# design1.net
KiCad netlist of a schematic drawn in EAGLE
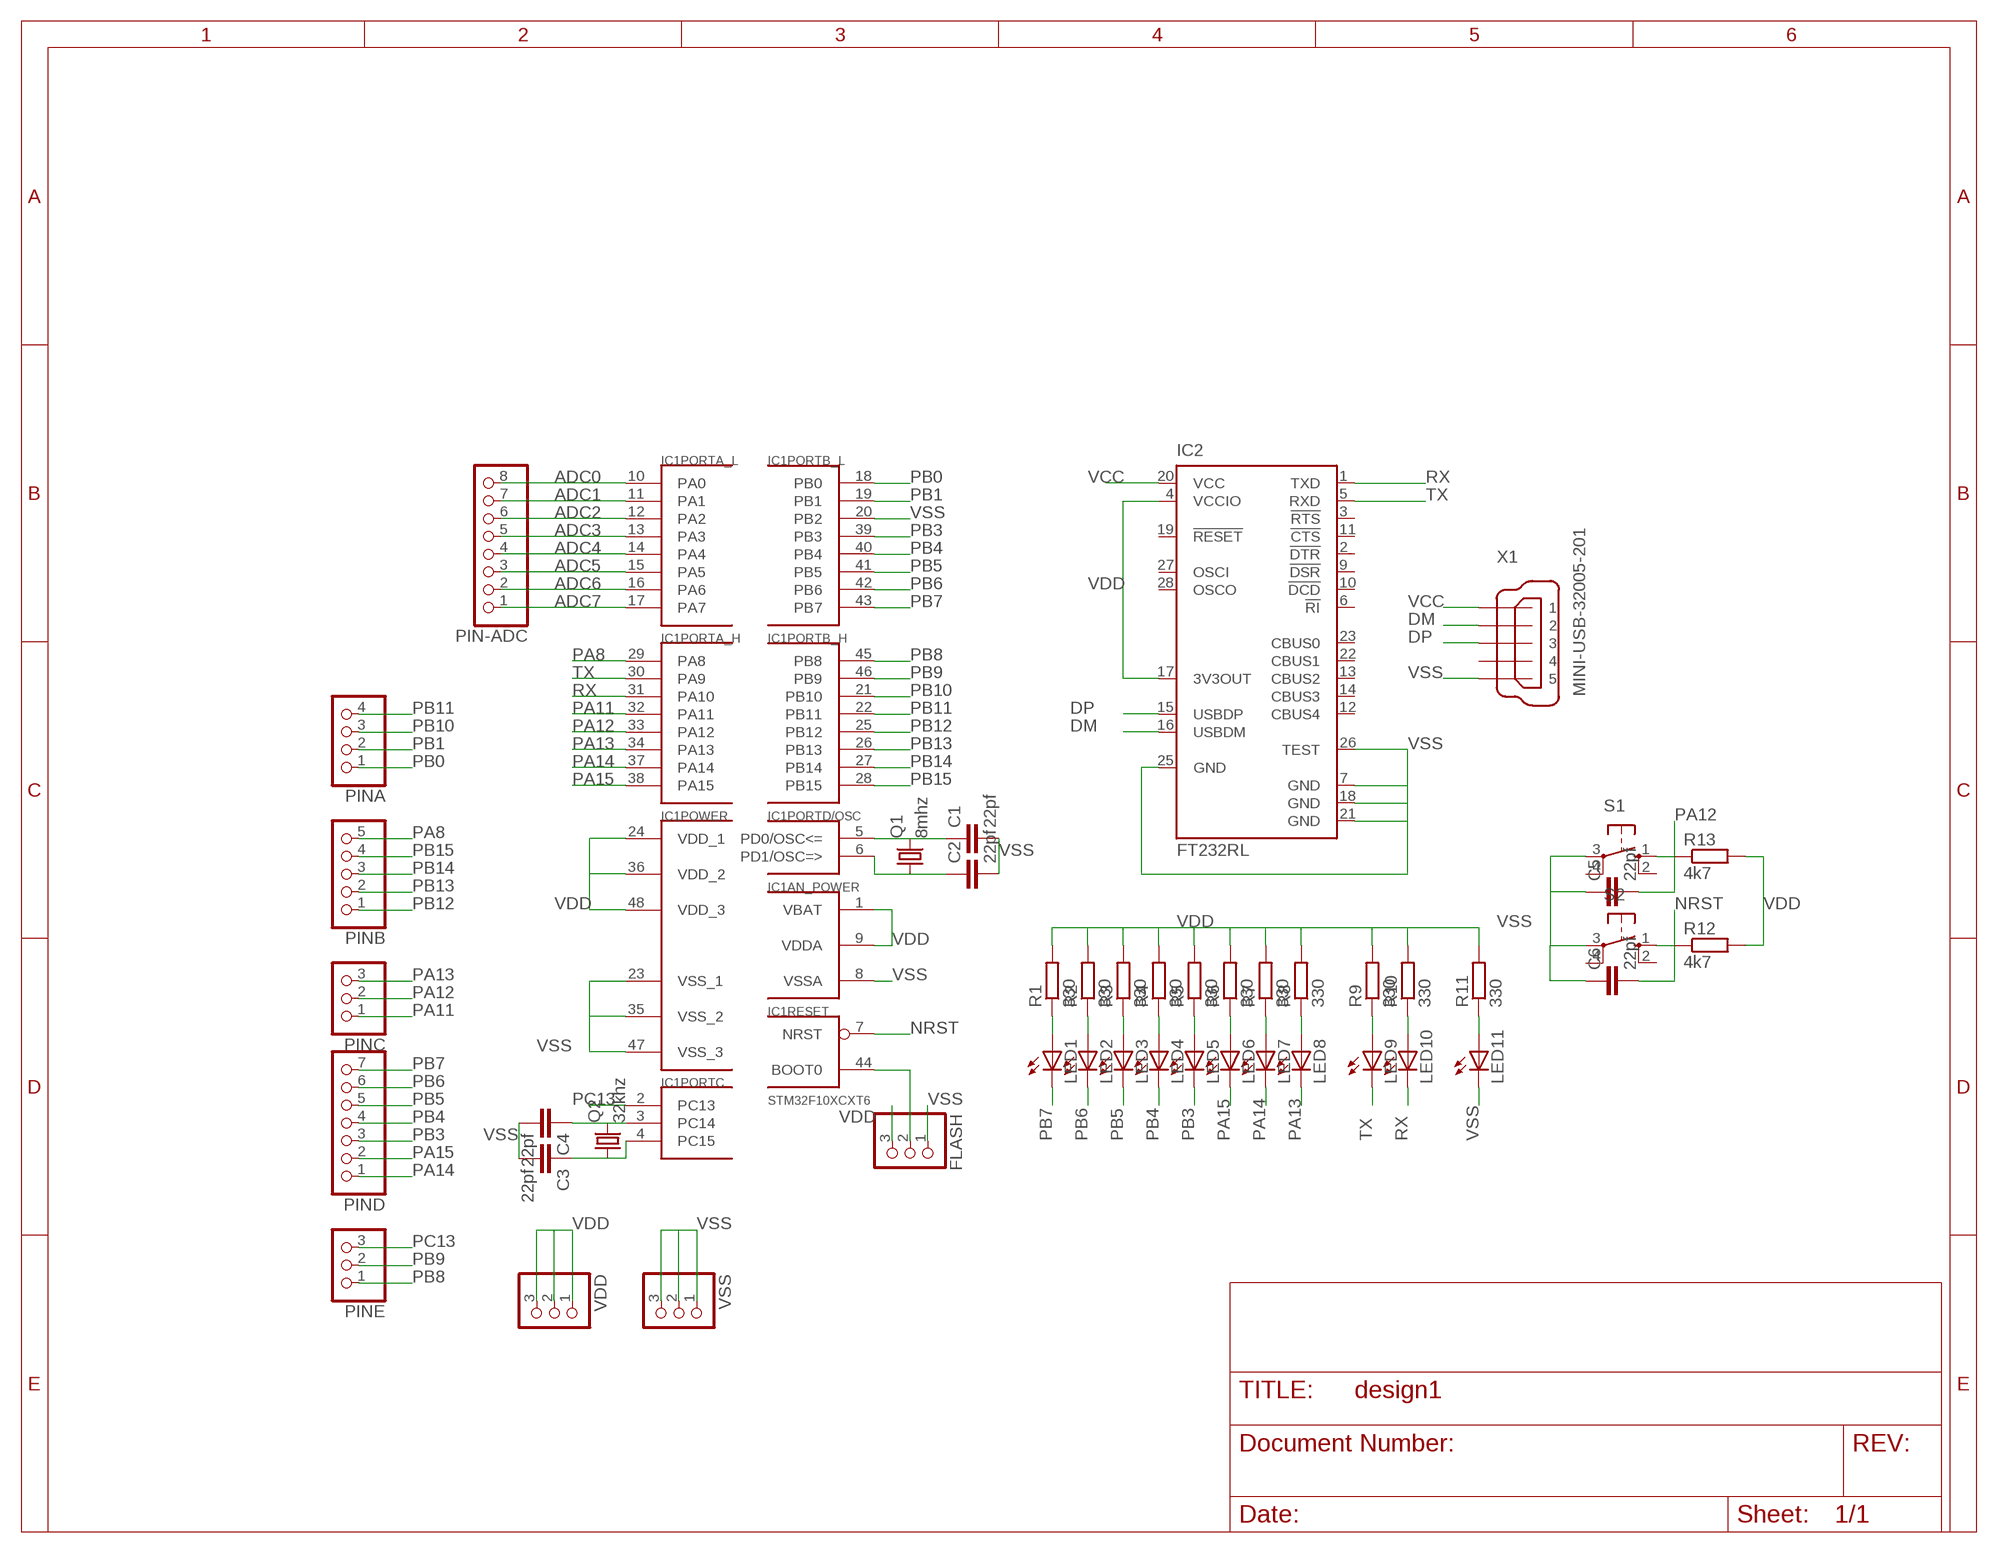
[diagram p0: schematic, sheet 1]

(export (version "E")
  (design (tool "Eeschema 10.0.6"))
  (components
    (comp (ref "C1")
      (value "22pf")
      (footprint "eagle-import:C1206")
      (libsource (lib "eagle-import") (part "C-EUC1206"))
    )
    (comp (ref "C2")
      (value "22pf")
      (footprint "eagle-import:C1206")
      (libsource (lib "eagle-import") (part "C-EUC1206"))
    )
    (comp (ref "C3")
      (value "22pf")
      (footprint "eagle-import:C1206")
      (libsource (lib "eagle-import") (part "C-EUC1206"))
    )
    (comp (ref "C4")
      (value "22pf")
      (footprint "eagle-import:C1206")
      (libsource (lib "eagle-import") (part "C-EUC1206"))
    )
    (comp (ref "C5")
      (value "22pf")
      (footprint "eagle-import:C1206")
      (libsource (lib "eagle-import") (part "C-EUC1206"))
    )
    (comp (ref "C6")
      (value "22pf")
      (footprint "eagle-import:C1206")
      (libsource (lib "eagle-import") (part "C-EUC1206"))
    )
    (comp (ref "FLASH")
      (value "PINHD-1X3")
      (footprint "eagle-import:1X03")
      (libsource (lib "eagle-import") (part "PINHD-1X3"))
    )
    (comp (ref "IC1")
      (value "STM32F10XCXT6")
      (footprint "eagle-import:TQFP48")
      (libsource (lib "eagle-import") (part "STM32F10XCXT6"))
    )
    (comp (ref "IC2")
      (value "FT232RL")
      (footprint "eagle-import:SSOP28")
      (libsource (lib "eagle-import") (part "FT232RL"))
    )
    (comp (ref "LED1")
      (value "LEDSML1206")
      (footprint "eagle-import:SML1206")
      (libsource (lib "eagle-import") (part "LEDSML1206"))
    )
    (comp (ref "LED2")
      (value "LEDSML1206")
      (footprint "eagle-import:SML1206")
      (libsource (lib "eagle-import") (part "LEDSML1206"))
    )
    (comp (ref "LED3")
      (value "LEDSML1206")
      (footprint "eagle-import:SML1206")
      (libsource (lib "eagle-import") (part "LEDSML1206"))
    )
    (comp (ref "LED4")
      (value "LEDSML1206")
      (footprint "eagle-import:SML1206")
      (libsource (lib "eagle-import") (part "LEDSML1206"))
    )
    (comp (ref "LED5")
      (value "LEDSML1206")
      (footprint "eagle-import:SML1206")
      (libsource (lib "eagle-import") (part "LEDSML1206"))
    )
    (comp (ref "LED6")
      (value "LEDSML1206")
      (footprint "eagle-import:SML1206")
      (libsource (lib "eagle-import") (part "LEDSML1206"))
    )
    (comp (ref "LED7")
      (value "LEDSML1206")
      (footprint "eagle-import:SML1206")
      (libsource (lib "eagle-import") (part "LEDSML1206"))
    )
    (comp (ref "LED8")
      (value "LEDSML1206")
      (footprint "eagle-import:SML1206")
      (libsource (lib "eagle-import") (part "LEDSML1206"))
    )
    (comp (ref "LED9")
      (value "LEDSML1206")
      (footprint "eagle-import:SML1206")
      (libsource (lib "eagle-import") (part "LEDSML1206"))
    )
    (comp (ref "LED10")
      (value "LEDSML1206")
      (footprint "eagle-import:SML1206")
      (libsource (lib "eagle-import") (part "LEDSML1206"))
    )
    (comp (ref "LED11")
      (value "LEDSML1206")
      (footprint "eagle-import:SML1206")
      (libsource (lib "eagle-import") (part "LEDSML1206"))
    )
    (comp (ref "PIN-ADC")
      (value "PINHD-1X8")
      (footprint "eagle-import:1X08")
      (libsource (lib "eagle-import") (part "PINHD-1X8"))
    )
    (comp (ref "PINA")
      (value "PINHD-1X4")
      (footprint "eagle-import:1X04")
      (libsource (lib "eagle-import") (part "PINHD-1X4"))
    )
    (comp (ref "PINB")
      (value "PINHD-1X5")
      (footprint "eagle-import:1X05")
      (libsource (lib "eagle-import") (part "PINHD-1X5"))
    )
    (comp (ref "PINC")
      (value "PINHD-1X3")
      (footprint "eagle-import:1X03")
      (libsource (lib "eagle-import") (part "PINHD-1X3"))
    )
    (comp (ref "PIND")
      (value "PINHD-1X7")
      (footprint "eagle-import:1X07")
      (libsource (lib "eagle-import") (part "PINHD-1X7"))
    )
    (comp (ref "PINE")
      (value "PINHD-1X3")
      (footprint "eagle-import:1X03")
      (libsource (lib "eagle-import") (part "PINHD-1X3"))
    )
    (comp (ref "Q1")
      (value "8mhz")
      (footprint "eagle-import:HC49U-V")
      (libsource (lib "eagle-import") (part "CRYSTALHC49U-V"))
    )
    (comp (ref "Q2")
      (value "32khz")
      (footprint "eagle-import:TC26V")
      (libsource (lib "eagle-import") (part "CRYSTALTC26V"))
    )
    (comp (ref "R1")
      (value "330")
      (footprint "eagle-import:R1206")
      (libsource (lib "eagle-import") (part "R-EU_R1206"))
    )
    (comp (ref "R2")
      (value "330")
      (footprint "eagle-import:R1206")
      (libsource (lib "eagle-import") (part "R-EU_R1206"))
    )
    (comp (ref "R3")
      (value "330")
      (footprint "eagle-import:R1206")
      (libsource (lib "eagle-import") (part "R-EU_R1206"))
    )
    (comp (ref "R4")
      (value "330")
      (footprint "eagle-import:R1206")
      (libsource (lib "eagle-import") (part "R-EU_R1206"))
    )
    (comp (ref "R5")
      (value "330")
      (footprint "eagle-import:R1206")
      (libsource (lib "eagle-import") (part "R-EU_R1206"))
    )
    (comp (ref "R6")
      (value "330")
      (footprint "eagle-import:R1206")
      (libsource (lib "eagle-import") (part "R-EU_R1206"))
    )
    (comp (ref "R7")
      (value "330")
      (footprint "eagle-import:R1206")
      (libsource (lib "eagle-import") (part "R-EU_R1206"))
    )
    (comp (ref "R8")
      (value "330")
      (footprint "eagle-import:R1206")
      (libsource (lib "eagle-import") (part "R-EU_R1206"))
    )
    (comp (ref "R9")
      (value "330")
      (footprint "eagle-import:R1206")
      (libsource (lib "eagle-import") (part "R-EU_R1206"))
    )
    (comp (ref "R10")
      (value "330")
      (footprint "eagle-import:R1206")
      (libsource (lib "eagle-import") (part "R-EU_R1206"))
    )
    (comp (ref "R11")
      (value "330")
      (footprint "eagle-import:R1206")
      (libsource (lib "eagle-import") (part "R-EU_R1206"))
    )
    (comp (ref "R12")
      (value "4k7")
      (footprint "eagle-import:R1206")
      (libsource (lib "eagle-import") (part "R-EU_R1206"))
    )
    (comp (ref "R13")
      (value "4k7")
      (footprint "eagle-import:R1206")
      (libsource (lib "eagle-import") (part "R-EU_R1206"))
    )
    (comp (ref "S1")
      (value "10-XX")
      (footprint "eagle-import:B3F-10XX")
      (fields (field (name "MPN") "B3F-1000"))
      (libsource (lib "eagle-import") (part "10-XX"))
    )
    (comp (ref "S2")
      (value "10-XX")
      (footprint "eagle-import:B3F-10XX")
      (fields (field (name "MPN") "B3F-1000"))
      (libsource (lib "eagle-import") (part "10-XX"))
    )
    (comp (ref "VDD")
      (value "PINHD-1X3")
      (footprint "eagle-import:1X03")
      (libsource (lib "eagle-import") (part "PINHD-1X3"))
    )
    (comp (ref "VSS")
      (value "PINHD-1X3")
      (footprint "eagle-import:1X03")
      (libsource (lib "eagle-import") (part "PINHD-1X3"))
    )
    (comp (ref "X1")
      (value "MINI-USB-32005-201")
      (footprint "eagle-import:32005-201")
      (libsource (lib "eagle-import") (part "MINI-USB-32005-201"))
    )
  )
  (nets
    (net (code "1") (name "/ADC0") (class "Default")
      (node (ref "IC1") (pin "10") (pinfunction "PA0_10") (pintype "bidirectional"))
      (node (ref "PIN-ADC") (pin "8") (pinfunction "8_8") (pintype "passive"))
    )
    (net (code "2") (name "/ADC1") (class "Default")
      (node (ref "IC1") (pin "11") (pinfunction "PA1_11") (pintype "bidirectional"))
      (node (ref "PIN-ADC") (pin "7") (pinfunction "7_7") (pintype "passive"))
    )
    (net (code "3") (name "/ADC2") (class "Default")
      (node (ref "IC1") (pin "12") (pinfunction "PA2_12") (pintype "bidirectional"))
      (node (ref "PIN-ADC") (pin "6") (pinfunction "6_6") (pintype "passive"))
    )
    (net (code "4") (name "/ADC3") (class "Default")
      (node (ref "IC1") (pin "13") (pinfunction "PA3_13") (pintype "bidirectional"))
      (node (ref "PIN-ADC") (pin "5") (pinfunction "5_5") (pintype "passive"))
    )
    (net (code "5") (name "/ADC4") (class "Default")
      (node (ref "IC1") (pin "14") (pinfunction "PA4_14") (pintype "bidirectional"))
      (node (ref "PIN-ADC") (pin "4") (pinfunction "4_4") (pintype "passive"))
    )
    (net (code "6") (name "/ADC5") (class "Default")
      (node (ref "IC1") (pin "15") (pinfunction "PA5_15") (pintype "bidirectional"))
      (node (ref "PIN-ADC") (pin "3") (pinfunction "3_3") (pintype "passive"))
    )
    (net (code "7") (name "/ADC6") (class "Default")
      (node (ref "IC1") (pin "16") (pinfunction "PA6_16") (pintype "bidirectional"))
      (node (ref "PIN-ADC") (pin "2") (pinfunction "2_2") (pintype "passive"))
    )
    (net (code "8") (name "/ADC7") (class "Default")
      (node (ref "IC1") (pin "17") (pinfunction "PA7_17") (pintype "bidirectional"))
      (node (ref "PIN-ADC") (pin "1") (pinfunction "1_1") (pintype "passive"))
    )
    (net (code "9") (name "/DM") (class "Default")
      (node (ref "IC2") (pin "16") (pinfunction "USBDM_16") (pintype "bidirectional"))
      (node (ref "X1") (pin "2") (pinfunction "2_2") (pintype "passive"))
    )
    (net (code "10") (name "/DP") (class "Default")
      (node (ref "IC2") (pin "15") (pinfunction "USBDP_15") (pintype "bidirectional"))
      (node (ref "X1") (pin "3") (pinfunction "3_3") (pintype "passive"))
    )
    (net (code "11") (name "/NRST") (class "Default")
      (node (ref "C6") (pin "2") (pinfunction "2_2") (pintype "passive"))
      (node (ref "IC1") (pin "7") (pinfunction "NRST_7") (pintype "input"))
      (node (ref "R12") (pin "1") (pinfunction "1_1") (pintype "passive"))
      (node (ref "S2") (pin "1") (pinfunction "S_1") (pintype "passive"))
    )
    (net (code "12") (name "/PA8") (class "Default")
      (node (ref "IC1") (pin "29") (pinfunction "PA8_29") (pintype "bidirectional"))
      (node (ref "PINB") (pin "5") (pinfunction "5_5") (pintype "passive"))
    )
    (net (code "13") (name "/PA11") (class "Default")
      (node (ref "IC1") (pin "32") (pinfunction "PA11_32") (pintype "bidirectional"))
      (node (ref "PINC") (pin "1") (pinfunction "1_1") (pintype "passive"))
    )
    (net (code "14") (name "/PA12") (class "Default")
      (node (ref "C5") (pin "2") (pinfunction "2_2") (pintype "passive"))
      (node (ref "IC1") (pin "33") (pinfunction "PA12_33") (pintype "bidirectional"))
      (node (ref "PINC") (pin "2") (pinfunction "2_2") (pintype "passive"))
      (node (ref "R13") (pin "1") (pinfunction "1_1") (pintype "passive"))
      (node (ref "S1") (pin "1") (pinfunction "S_1") (pintype "passive"))
    )
    (net (code "15") (name "/PA13") (class "Default")
      (node (ref "IC1") (pin "34") (pinfunction "PA13_34") (pintype "bidirectional"))
      (node (ref "LED8") (pin "C") (pinfunction "C_C") (pintype "passive"))
      (node (ref "PINC") (pin "3") (pinfunction "3_3") (pintype "passive"))
    )
    (net (code "16") (name "/PA14") (class "Default")
      (node (ref "IC1") (pin "37") (pinfunction "PA14_37") (pintype "bidirectional"))
      (node (ref "LED7") (pin "C") (pinfunction "C_C") (pintype "passive"))
      (node (ref "PIND") (pin "1") (pinfunction "1_1") (pintype "passive"))
    )
    (net (code "17") (name "/PA15") (class "Default")
      (node (ref "IC1") (pin "38") (pinfunction "PA15_38") (pintype "bidirectional"))
      (node (ref "LED6") (pin "C") (pinfunction "C_C") (pintype "passive"))
      (node (ref "PIND") (pin "2") (pinfunction "2_2") (pintype "passive"))
    )
    (net (code "18") (name "/PB0") (class "Default")
      (node (ref "IC1") (pin "18") (pinfunction "PB0_18") (pintype "bidirectional"))
      (node (ref "PINA") (pin "1") (pinfunction "1_1") (pintype "passive"))
    )
    (net (code "19") (name "/PB1") (class "Default")
      (node (ref "IC1") (pin "19") (pinfunction "PB1_19") (pintype "bidirectional"))
      (node (ref "PINA") (pin "2") (pinfunction "2_2") (pintype "passive"))
    )
    (net (code "20") (name "/PB3") (class "Default")
      (node (ref "IC1") (pin "39") (pinfunction "PB3_39") (pintype "bidirectional"))
      (node (ref "LED5") (pin "C") (pinfunction "C_C") (pintype "passive"))
      (node (ref "PIND") (pin "3") (pinfunction "3_3") (pintype "passive"))
    )
    (net (code "21") (name "/PB4") (class "Default")
      (node (ref "IC1") (pin "40") (pinfunction "PB4_40") (pintype "bidirectional"))
      (node (ref "LED4") (pin "C") (pinfunction "C_C") (pintype "passive"))
      (node (ref "PIND") (pin "4") (pinfunction "4_4") (pintype "passive"))
    )
    (net (code "22") (name "/PB5") (class "Default")
      (node (ref "IC1") (pin "41") (pinfunction "PB5_41") (pintype "bidirectional"))
      (node (ref "LED3") (pin "C") (pinfunction "C_C") (pintype "passive"))
      (node (ref "PIND") (pin "5") (pinfunction "5_5") (pintype "passive"))
    )
    (net (code "23") (name "/PB6") (class "Default")
      (node (ref "IC1") (pin "42") (pinfunction "PB6_42") (pintype "bidirectional"))
      (node (ref "LED2") (pin "C") (pinfunction "C_C") (pintype "passive"))
      (node (ref "PIND") (pin "6") (pinfunction "6_6") (pintype "passive"))
    )
    (net (code "24") (name "/PB7") (class "Default")
      (node (ref "IC1") (pin "43") (pinfunction "PB7_43") (pintype "bidirectional"))
      (node (ref "LED1") (pin "C") (pinfunction "C_C") (pintype "passive"))
      (node (ref "PIND") (pin "7") (pinfunction "7_7") (pintype "passive"))
    )
    (net (code "25") (name "/PB8") (class "Default")
      (node (ref "IC1") (pin "45") (pinfunction "PB8_45") (pintype "bidirectional"))
      (node (ref "PINE") (pin "1") (pinfunction "1_1") (pintype "passive"))
    )
    (net (code "26") (name "/PB9") (class "Default")
      (node (ref "IC1") (pin "46") (pinfunction "PB9_46") (pintype "bidirectional"))
      (node (ref "PINE") (pin "2") (pinfunction "2_2") (pintype "passive"))
    )
    (net (code "27") (name "/PB10") (class "Default")
      (node (ref "IC1") (pin "21") (pinfunction "PB10_21") (pintype "bidirectional"))
      (node (ref "PINA") (pin "3") (pinfunction "3_3") (pintype "passive"))
    )
    (net (code "28") (name "/PB11") (class "Default")
      (node (ref "IC1") (pin "22") (pinfunction "PB11_22") (pintype "bidirectional"))
      (node (ref "PINA") (pin "4") (pinfunction "4_4") (pintype "passive"))
    )
    (net (code "29") (name "/PB12") (class "Default")
      (node (ref "IC1") (pin "25") (pinfunction "PB12_25") (pintype "bidirectional"))
      (node (ref "PINB") (pin "1") (pinfunction "1_1") (pintype "passive"))
    )
    (net (code "30") (name "/PB13") (class "Default")
      (node (ref "IC1") (pin "26") (pinfunction "PB13_26") (pintype "bidirectional"))
      (node (ref "PINB") (pin "2") (pinfunction "2_2") (pintype "passive"))
    )
    (net (code "31") (name "/PB14") (class "Default")
      (node (ref "IC1") (pin "27") (pinfunction "PB14_27") (pintype "bidirectional"))
      (node (ref "PINB") (pin "3") (pinfunction "3_3") (pintype "passive"))
    )
    (net (code "32") (name "/PB15") (class "Default")
      (node (ref "IC1") (pin "28") (pinfunction "PB15_28") (pintype "bidirectional"))
      (node (ref "PINB") (pin "4") (pinfunction "4_4") (pintype "passive"))
    )
    (net (code "33") (name "/PC13") (class "Default")
      (node (ref "IC1") (pin "2") (pinfunction "PC13_2") (pintype "bidirectional"))
      (node (ref "PINE") (pin "3") (pinfunction "3_3") (pintype "passive"))
    )
    (net (code "34") (name "/RX") (class "Default")
      (node (ref "IC1") (pin "31") (pinfunction "PA10_31") (pintype "bidirectional"))
      (node (ref "IC2") (pin "1") (pinfunction "TXD_1") (pintype "output"))
      (node (ref "LED10") (pin "C") (pinfunction "C_C") (pintype "passive"))
    )
    (net (code "35") (name "/TX") (class "Default")
      (node (ref "IC1") (pin "30") (pinfunction "PA9_30") (pintype "bidirectional"))
      (node (ref "IC2") (pin "5") (pinfunction "RXD_5") (pintype "input"))
      (node (ref "LED9") (pin "C") (pinfunction "C_C") (pintype "passive"))
    )
    (net (code "36") (name "/VCC") (class "Default")
      (node (ref "IC2") (pin "20") (pinfunction "VCC_20") (pintype "power_in"))
      (node (ref "X1") (pin "1") (pinfunction "1_1") (pintype "passive"))
    )
    (net (code "37") (name "/VDD") (class "Default")
      (node (ref "FLASH") (pin "3") (pinfunction "3_3") (pintype "passive"))
      (node (ref "IC1") (pin "1") (pinfunction "VBAT_1") (pintype "power_in"))
      (node (ref "IC1") (pin "24") (pinfunction "VDD_1_24") (pintype "power_in"))
      (node (ref "IC1") (pin "36") (pinfunction "VDD_2_36") (pintype "power_in"))
      (node (ref "IC1") (pin "48") (pinfunction "VDD_3_48") (pintype "power_in"))
      (node (ref "IC1") (pin "9") (pinfunction "VDDA_9") (pintype "power_in"))
      (node (ref "IC2") (pin "17") (pinfunction "3V3OUT_17") (pintype "output"))
      (node (ref "IC2") (pin "4") (pinfunction "VCCIO_4") (pintype "power_in"))
      (node (ref "R1") (pin "2") (pinfunction "2_2") (pintype "passive"))
      (node (ref "R10") (pin "2") (pinfunction "2_2") (pintype "passive"))
      (node (ref "R11") (pin "2") (pinfunction "2_2") (pintype "passive"))
      (node (ref "R12") (pin "2") (pinfunction "2_2") (pintype "passive"))
      (node (ref "R13") (pin "2") (pinfunction "2_2") (pintype "passive"))
      (node (ref "R2") (pin "2") (pinfunction "2_2") (pintype "passive"))
      (node (ref "R3") (pin "2") (pinfunction "2_2") (pintype "passive"))
      (node (ref "R4") (pin "2") (pinfunction "2_2") (pintype "passive"))
      (node (ref "R5") (pin "2") (pinfunction "2_2") (pintype "passive"))
      (node (ref "R6") (pin "2") (pinfunction "2_2") (pintype "passive"))
      (node (ref "R7") (pin "2") (pinfunction "2_2") (pintype "passive"))
      (node (ref "R8") (pin "2") (pinfunction "2_2") (pintype "passive"))
      (node (ref "R9") (pin "2") (pinfunction "2_2") (pintype "passive"))
      (node (ref "VDD") (pin "1") (pinfunction "1_1") (pintype "passive"))
      (node (ref "VDD") (pin "2") (pinfunction "2_2") (pintype "passive"))
      (node (ref "VDD") (pin "3") (pinfunction "3_3") (pintype "passive"))
    )
    (net (code "38") (name "/VSS") (class "Default")
      (node (ref "C1") (pin "2") (pinfunction "2_2") (pintype "passive"))
      (node (ref "C2") (pin "2") (pinfunction "2_2") (pintype "passive"))
      (node (ref "C3") (pin "2") (pinfunction "2_2") (pintype "passive"))
      (node (ref "C4") (pin "2") (pinfunction "2_2") (pintype "passive"))
      (node (ref "C5") (pin "1") (pinfunction "1_1") (pintype "passive"))
      (node (ref "C6") (pin "1") (pinfunction "1_1") (pintype "passive"))
      (node (ref "FLASH") (pin "1") (pinfunction "1_1") (pintype "passive"))
      (node (ref "IC1") (pin "20") (pinfunction "PB2_20") (pintype "bidirectional"))
      (node (ref "IC1") (pin "23") (pinfunction "VSS_1_23") (pintype "power_in"))
      (node (ref "IC1") (pin "35") (pinfunction "VSS_2_35") (pintype "power_in"))
      (node (ref "IC1") (pin "47") (pinfunction "VSS_3_47") (pintype "power_in"))
      (node (ref "IC1") (pin "8") (pinfunction "VSSA_8") (pintype "power_in"))
      (node (ref "IC2") (pin "18") (pinfunction "GND_18") (pintype "power_in"))
      (node (ref "IC2") (pin "21") (pinfunction "GND_21") (pintype "power_in"))
      (node (ref "IC2") (pin "25") (pinfunction "GND_25") (pintype "power_in"))
      (node (ref "IC2") (pin "26") (pinfunction "TEST_26") (pintype "input"))
      (node (ref "IC2") (pin "7") (pinfunction "GND_7") (pintype "power_in"))
      (node (ref "LED11") (pin "C") (pinfunction "C_C") (pintype "passive"))
      (node (ref "S1") (pin "3") (pinfunction "P_3") (pintype "passive"))
      (node (ref "S2") (pin "3") (pinfunction "P_3") (pintype "passive"))
      (node (ref "VSS") (pin "1") (pinfunction "1_1") (pintype "passive"))
      (node (ref "VSS") (pin "2") (pinfunction "2_2") (pintype "passive"))
      (node (ref "VSS") (pin "3") (pinfunction "3_3") (pintype "passive"))
      (node (ref "X1") (pin "5") (pinfunction "5_5") (pintype "passive"))
    )
    (net (code "39") (name "Net-(IC1F-PC14)") (class "Default")
      (node (ref "C4") (pin "1") (pinfunction "1_1") (pintype "passive"))
      (node (ref "IC1") (pin "3") (pinfunction "PC14_3") (pintype "bidirectional"))
      (node (ref "Q2") (pin "2") (pinfunction "2_2") (pintype "passive"))
    )
    (net (code "40") (name "Net-(IC1F-PC15)") (class "Default")
      (node (ref "C3") (pin "1") (pinfunction "1_1") (pintype "passive"))
      (node (ref "IC1") (pin "4") (pinfunction "PC15_4") (pintype "bidirectional"))
      (node (ref "Q2") (pin "1") (pinfunction "1_1") (pintype "passive"))
    )
    (net (code "41") (name "Net-(IC1G-PD0{slash}OSC<=)") (class "Default")
      (node (ref "C1") (pin "1") (pinfunction "1_1") (pintype "passive"))
      (node (ref "IC1") (pin "5") (pinfunction "PD0/OSC<=_5") (pintype "bidirectional"))
      (node (ref "Q1") (pin "2") (pinfunction "2_2") (pintype "passive"))
    )
    (net (code "42") (name "Net-(IC1G-PD1{slash}OSC=>)") (class "Default")
      (node (ref "C2") (pin "1") (pinfunction "1_1") (pintype "passive"))
      (node (ref "IC1") (pin "6") (pinfunction "PD1/OSC=>_6") (pintype "bidirectional"))
      (node (ref "Q1") (pin "1") (pinfunction "1_1") (pintype "passive"))
    )
    (net (code "43") (name "Net-(IC1I-BOOT0)") (class "Default")
      (node (ref "FLASH") (pin "2") (pinfunction "2_2") (pintype "passive"))
      (node (ref "IC1") (pin "44") (pinfunction "BOOT0_44") (pintype "input"))
    )
    (net (code "44") (name "Net-(LED1-PadA)") (class "Default")
      (node (ref "LED1") (pin "A") (pinfunction "A_A") (pintype "passive"))
      (node (ref "R1") (pin "1") (pinfunction "1_1") (pintype "passive"))
    )
    (net (code "45") (name "Net-(LED2-PadA)") (class "Default")
      (node (ref "LED2") (pin "A") (pinfunction "A_A") (pintype "passive"))
      (node (ref "R2") (pin "1") (pinfunction "1_1") (pintype "passive"))
    )
    (net (code "46") (name "Net-(LED3-PadA)") (class "Default")
      (node (ref "LED3") (pin "A") (pinfunction "A_A") (pintype "passive"))
      (node (ref "R3") (pin "1") (pinfunction "1_1") (pintype "passive"))
    )
    (net (code "47") (name "Net-(LED4-PadA)") (class "Default")
      (node (ref "LED4") (pin "A") (pinfunction "A_A") (pintype "passive"))
      (node (ref "R4") (pin "1") (pinfunction "1_1") (pintype "passive"))
    )
    (net (code "48") (name "Net-(LED5-PadA)") (class "Default")
      (node (ref "LED5") (pin "A") (pinfunction "A_A") (pintype "passive"))
      (node (ref "R5") (pin "1") (pinfunction "1_1") (pintype "passive"))
    )
    (net (code "49") (name "Net-(LED6-PadA)") (class "Default")
      (node (ref "LED6") (pin "A") (pinfunction "A_A") (pintype "passive"))
      (node (ref "R6") (pin "1") (pinfunction "1_1") (pintype "passive"))
    )
    (net (code "50") (name "Net-(LED7-PadA)") (class "Default")
      (node (ref "LED7") (pin "A") (pinfunction "A_A") (pintype "passive"))
      (node (ref "R7") (pin "1") (pinfunction "1_1") (pintype "passive"))
    )
    (net (code "51") (name "Net-(LED8-PadA)") (class "Default")
      (node (ref "LED8") (pin "A") (pinfunction "A_A") (pintype "passive"))
      (node (ref "R8") (pin "1") (pinfunction "1_1") (pintype "passive"))
    )
    (net (code "52") (name "Net-(LED9-PadA)") (class "Default")
      (node (ref "LED9") (pin "A") (pinfunction "A_A") (pintype "passive"))
      (node (ref "R9") (pin "1") (pinfunction "1_1") (pintype "passive"))
    )
    (net (code "53") (name "Net-(LED10-PadA)") (class "Default")
      (node (ref "LED10") (pin "A") (pinfunction "A_A") (pintype "passive"))
      (node (ref "R10") (pin "1") (pinfunction "1_1") (pintype "passive"))
    )
    (net (code "54") (name "Net-(LED11-PadA)") (class "Default")
      (node (ref "LED11") (pin "A") (pinfunction "A_A") (pintype "passive"))
      (node (ref "R11") (pin "1") (pinfunction "1_1") (pintype "passive"))
    )
    (net (code "55") (name "unconnected-(IC2-CBUS0-Pad23)") (class "Default")
      (node (ref "IC2") (pin "23") (pinfunction "CBUS0_23") (pintype "bidirectional"))
    )
    (net (code "56") (name "unconnected-(IC2-CBUS1-Pad22)") (class "Default")
      (node (ref "IC2") (pin "22") (pinfunction "CBUS1_22") (pintype "bidirectional"))
    )
    (net (code "57") (name "unconnected-(IC2-CBUS2-Pad13)") (class "Default")
      (node (ref "IC2") (pin "13") (pinfunction "CBUS2_13") (pintype "bidirectional"))
    )
    (net (code "58") (name "unconnected-(IC2-CBUS3-Pad14)") (class "Default")
      (node (ref "IC2") (pin "14") (pinfunction "CBUS3_14") (pintype "bidirectional"))
    )
    (net (code "59") (name "unconnected-(IC2-CBUS4-Pad12)") (class "Default")
      (node (ref "IC2") (pin "12") (pinfunction "CBUS4_12") (pintype "bidirectional"))
    )
    (net (code "60") (name "unconnected-(IC2-OSCI-Pad27)") (class "Default")
      (node (ref "IC2") (pin "27") (pinfunction "OSCI_27") (pintype "input"))
    )
    (net (code "61") (name "unconnected-(IC2-OSCO-Pad28)") (class "Default")
      (node (ref "IC2") (pin "28") (pinfunction "OSCO_28") (pintype "output"))
    )
    (net (code "62") (name "unconnected-(IC2-~{CTS}-Pad11)") (class "Default")
      (node (ref "IC2") (pin "11") (pinfunction "~{CTS}_11") (pintype "input"))
    )
    (net (code "63") (name "unconnected-(IC2-~{DCD}-Pad10)") (class "Default")
      (node (ref "IC2") (pin "10") (pinfunction "~{DCD}_10") (pintype "input"))
    )
    (net (code "64") (name "unconnected-(IC2-~{DSR}-Pad9)") (class "Default")
      (node (ref "IC2") (pin "9") (pinfunction "~{DSR}_9") (pintype "input"))
    )
    (net (code "65") (name "unconnected-(IC2-~{DTR}-Pad2)") (class "Default")
      (node (ref "IC2") (pin "2") (pinfunction "~{DTR}_2") (pintype "output"))
    )
    (net (code "66") (name "unconnected-(IC2-~{RESET}-Pad19)") (class "Default")
      (node (ref "IC2") (pin "19") (pinfunction "~{RESET}_19") (pintype "input"))
    )
    (net (code "67") (name "unconnected-(IC2-~{RI}-Pad6)") (class "Default")
      (node (ref "IC2") (pin "6") (pinfunction "~{RI}_6") (pintype "input"))
    )
    (net (code "68") (name "unconnected-(IC2-~{RTS}-Pad3)") (class "Default")
      (node (ref "IC2") (pin "3") (pinfunction "~{RTS}_3") (pintype "output"))
    )
    (net (code "69") (name "unconnected-(S1-P1-Pad4)") (class "Default")
      (node (ref "S1") (pin "4") (pinfunction "P1_4") (pintype "passive"))
    )
    (net (code "70") (name "unconnected-(S1-S1-Pad2)") (class "Default")
      (node (ref "S1") (pin "2") (pinfunction "S1_2") (pintype "passive"))
    )
    (net (code "71") (name "unconnected-(S2-P1-Pad4)") (class "Default")
      (node (ref "S2") (pin "4") (pinfunction "P1_4") (pintype "passive"))
    )
    (net (code "72") (name "unconnected-(S2-S1-Pad2)") (class "Default")
      (node (ref "S2") (pin "2") (pinfunction "S1_2") (pintype "passive"))
    )
    (net (code "73") (name "unconnected-(X1-Pad4)") (class "Default")
      (node (ref "X1") (pin "4") (pinfunction "4_4") (pintype "passive"))
    )
  )
)
